# FBMiniLEDStrip.net
KiCad netlist of a schematic drawn in EAGLE
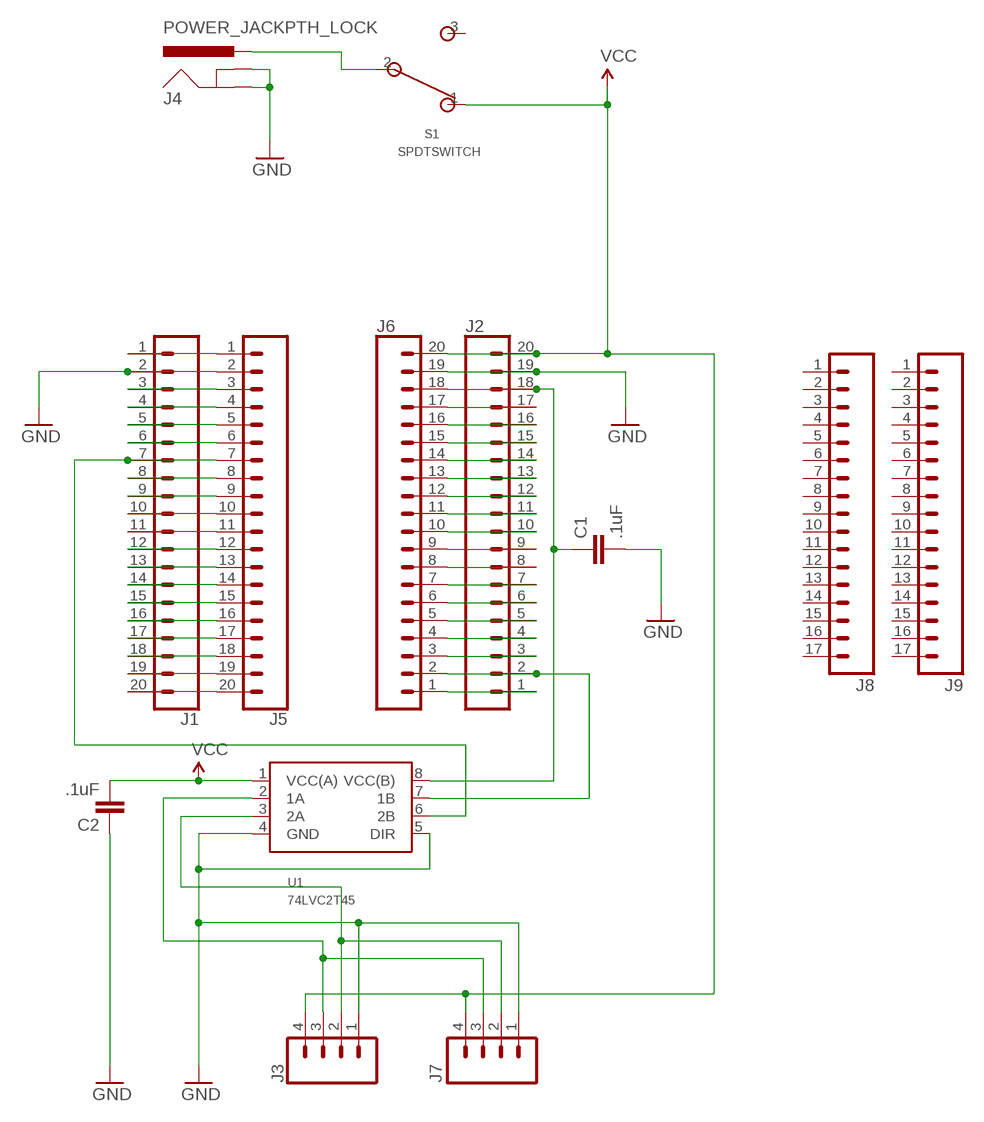
[diagram p0: schematic, sheet 1]

(export (version "E")
  (design (tool "Eeschema 10.0.6"))
  (components
    (comp (ref "C1")
      (value ".1uF")
      (footprint "eagle-import:0603-CAP")
      (libsource (lib "eagle-import") (part "CAP0603-CAP"))
    )
    (comp (ref "C2")
      (value ".1uF")
      (footprint "eagle-import:0603-CAP")
      (libsource (lib "eagle-import") (part "CAP0603-CAP"))
    )
    (comp (ref "J1")
      (value "CONN_20")
      (footprint "eagle-import:1X20")
      (libsource (lib "eagle-import") (part "CONN_20"))
    )
    (comp (ref "J2")
      (value "CONN_20")
      (footprint "eagle-import:1X20")
      (libsource (lib "eagle-import") (part "CONN_20"))
    )
    (comp (ref "J3")
      (value "CONN_04SCREW")
      (footprint "eagle-import:SCREWTERMINAL-3.5MM-4@1")
      (libsource (lib "eagle-import") (part "CONN_04SCREW"))
    )
    (comp (ref "J4")
      (value "POWER_JACKPTH_LOCK")
      (footprint "eagle-import:POWER_JACK_PTH_LOCK")
      (libsource (lib "eagle-import") (part "POWER_JACKPTH_LOCK"))
    )
    (comp (ref "J5")
      (value "CONN_20")
      (footprint "eagle-import:1X20")
      (libsource (lib "eagle-import") (part "CONN_20"))
    )
    (comp (ref "J6")
      (value "CONN_20")
      (footprint "eagle-import:1X20")
      (libsource (lib "eagle-import") (part "CONN_20"))
    )
    (comp (ref "J7")
      (value "M04PTH")
      (footprint "eagle-import:1X04")
      (libsource (lib "eagle-import") (part "M04PTH"))
    )
    (comp (ref "J8")
      (value "M17")
      (footprint "eagle-import:1X17")
      (libsource (lib "eagle-import") (part "M17"))
    )
    (comp (ref "J9")
      (value "M17")
      (footprint "eagle-import:1X17")
      (libsource (lib "eagle-import") (part "M17"))
    )
    (comp (ref "S1")
      (value "SPDTSWITCH")
      (footprint "eagle-import:100SP1T1B4M2QE")
      (libsource (lib "eagle-import") (part "SPDTSWITCH"))
    )
    (comp (ref "U1")
      (value "74LVC2T45")
      (footprint "eagle-import:VSSOP8")
      (libsource (lib "eagle-import") (part "74LVC2T45"))
    )
  )
  (nets
    (net (code "1") (name "GND") (class "Default")
      (node (ref "C1") (pin "2") (pinfunction "2_2") (pintype "passive"))
      (node (ref "C2") (pin "1") (pinfunction "1_1") (pintype "passive"))
      (node (ref "J1") (pin "2") (pinfunction "2_2") (pintype "passive"))
      (node (ref "J2") (pin "19") (pinfunction "19_19") (pintype "passive"))
      (node (ref "J3") (pin "1") (pinfunction "1_1") (pintype "passive"))
      (node (ref "J4") (pin "GND") (pinfunction "GND_GND") (pintype "bidirectional"))
      (node (ref "J4") (pin "GNDBREAK") (pinfunction "GNDBREAK_GNDBREAK") (pintype "bidirectional"))
      (node (ref "J5") (pin "2") (pinfunction "2_2") (pintype "passive"))
      (node (ref "J6") (pin "19") (pinfunction "19_19") (pintype "passive"))
      (node (ref "J7") (pin "1") (pinfunction "1_1") (pintype "passive"))
      (node (ref "U1") (pin "4") (pinfunction "GND_4") (pintype "bidirectional"))
      (node (ref "U1") (pin "5") (pinfunction "DIR_5") (pintype "bidirectional"))
    )
    (net (code "2") (name "Net-(J1-Pad1)") (class "Default")
      (node (ref "J1") (pin "1") (pinfunction "1_1") (pintype "passive"))
      (node (ref "J5") (pin "1") (pinfunction "1_1") (pintype "passive"))
    )
    (net (code "3") (name "Net-(J1-Pad3)") (class "Default")
      (node (ref "J1") (pin "3") (pinfunction "3_3") (pintype "passive"))
      (node (ref "J5") (pin "3") (pinfunction "3_3") (pintype "passive"))
    )
    (net (code "4") (name "Net-(J1-Pad4)") (class "Default")
      (node (ref "J1") (pin "4") (pinfunction "4_4") (pintype "passive"))
      (node (ref "J5") (pin "4") (pinfunction "4_4") (pintype "passive"))
    )
    (net (code "5") (name "Net-(J1-Pad5)") (class "Default")
      (node (ref "J1") (pin "5") (pinfunction "5_5") (pintype "passive"))
      (node (ref "J5") (pin "5") (pinfunction "5_5") (pintype "passive"))
    )
    (net (code "6") (name "Net-(J1-Pad6)") (class "Default")
      (node (ref "J1") (pin "6") (pinfunction "6_6") (pintype "passive"))
      (node (ref "J5") (pin "6") (pinfunction "6_6") (pintype "passive"))
    )
    (net (code "7") (name "Net-(J1-Pad8)") (class "Default")
      (node (ref "J1") (pin "8") (pinfunction "8_8") (pintype "passive"))
      (node (ref "J5") (pin "8") (pinfunction "8_8") (pintype "passive"))
    )
    (net (code "8") (name "Net-(J1-Pad9)") (class "Default")
      (node (ref "J1") (pin "9") (pinfunction "9_9") (pintype "passive"))
      (node (ref "J5") (pin "9") (pinfunction "9_9") (pintype "passive"))
    )
    (net (code "9") (name "Net-(J1-Pad10)") (class "Default")
      (node (ref "J1") (pin "10") (pinfunction "10_10") (pintype "passive"))
      (node (ref "J5") (pin "10") (pinfunction "10_10") (pintype "passive"))
    )
    (net (code "10") (name "Net-(J1-Pad11)") (class "Default")
      (node (ref "J1") (pin "11") (pinfunction "11_11") (pintype "passive"))
      (node (ref "J5") (pin "11") (pinfunction "11_11") (pintype "passive"))
    )
    (net (code "11") (name "Net-(J1-Pad12)") (class "Default")
      (node (ref "J1") (pin "12") (pinfunction "12_12") (pintype "passive"))
      (node (ref "J5") (pin "12") (pinfunction "12_12") (pintype "passive"))
    )
    (net (code "12") (name "Net-(J1-Pad13)") (class "Default")
      (node (ref "J1") (pin "13") (pinfunction "13_13") (pintype "passive"))
      (node (ref "J5") (pin "13") (pinfunction "13_13") (pintype "passive"))
    )
    (net (code "13") (name "Net-(J1-Pad14)") (class "Default")
      (node (ref "J1") (pin "14") (pinfunction "14_14") (pintype "passive"))
      (node (ref "J5") (pin "14") (pinfunction "14_14") (pintype "passive"))
    )
    (net (code "14") (name "Net-(J1-Pad15)") (class "Default")
      (node (ref "J1") (pin "15") (pinfunction "15_15") (pintype "passive"))
      (node (ref "J5") (pin "15") (pinfunction "15_15") (pintype "passive"))
    )
    (net (code "15") (name "Net-(J1-Pad16)") (class "Default")
      (node (ref "J1") (pin "16") (pinfunction "16_16") (pintype "passive"))
      (node (ref "J5") (pin "16") (pinfunction "16_16") (pintype "passive"))
    )
    (net (code "16") (name "Net-(J1-Pad17)") (class "Default")
      (node (ref "J1") (pin "17") (pinfunction "17_17") (pintype "passive"))
      (node (ref "J5") (pin "17") (pinfunction "17_17") (pintype "passive"))
    )
    (net (code "17") (name "Net-(J1-Pad18)") (class "Default")
      (node (ref "J1") (pin "18") (pinfunction "18_18") (pintype "passive"))
      (node (ref "J5") (pin "18") (pinfunction "18_18") (pintype "passive"))
    )
    (net (code "18") (name "Net-(J1-Pad19)") (class "Default")
      (node (ref "J1") (pin "19") (pinfunction "19_19") (pintype "passive"))
      (node (ref "J5") (pin "19") (pinfunction "19_19") (pintype "passive"))
    )
    (net (code "19") (name "Net-(J1-Pad20)") (class "Default")
      (node (ref "J1") (pin "20") (pinfunction "20_20") (pintype "passive"))
      (node (ref "J5") (pin "20") (pinfunction "20_20") (pintype "passive"))
    )
    (net (code "20") (name "Net-(J2-Pad1)") (class "Default")
      (node (ref "J2") (pin "1") (pinfunction "1_1") (pintype "passive"))
      (node (ref "J6") (pin "1") (pinfunction "1_1") (pintype "passive"))
    )
    (net (code "21") (name "Net-(J2-Pad3)") (class "Default")
      (node (ref "J2") (pin "3") (pinfunction "3_3") (pintype "passive"))
      (node (ref "J6") (pin "3") (pinfunction "3_3") (pintype "passive"))
    )
    (net (code "22") (name "Net-(J2-Pad4)") (class "Default")
      (node (ref "J2") (pin "4") (pinfunction "4_4") (pintype "passive"))
      (node (ref "J6") (pin "4") (pinfunction "4_4") (pintype "passive"))
    )
    (net (code "23") (name "Net-(J2-Pad5)") (class "Default")
      (node (ref "J2") (pin "5") (pinfunction "5_5") (pintype "passive"))
      (node (ref "J6") (pin "5") (pinfunction "5_5") (pintype "passive"))
    )
    (net (code "24") (name "Net-(J2-Pad6)") (class "Default")
      (node (ref "J2") (pin "6") (pinfunction "6_6") (pintype "passive"))
      (node (ref "J6") (pin "6") (pinfunction "6_6") (pintype "passive"))
    )
    (net (code "25") (name "Net-(J2-Pad7)") (class "Default")
      (node (ref "J2") (pin "7") (pinfunction "7_7") (pintype "passive"))
      (node (ref "J6") (pin "7") (pinfunction "7_7") (pintype "passive"))
    )
    (net (code "26") (name "Net-(J2-Pad8)") (class "Default")
      (node (ref "J2") (pin "8") (pinfunction "8_8") (pintype "passive"))
      (node (ref "J6") (pin "8") (pinfunction "8_8") (pintype "passive"))
    )
    (net (code "27") (name "Net-(J2-Pad9)") (class "Default")
      (node (ref "J2") (pin "9") (pinfunction "9_9") (pintype "passive"))
      (node (ref "J6") (pin "9") (pinfunction "9_9") (pintype "passive"))
    )
    (net (code "28") (name "Net-(J2-Pad10)") (class "Default")
      (node (ref "J2") (pin "10") (pinfunction "10_10") (pintype "passive"))
      (node (ref "J6") (pin "10") (pinfunction "10_10") (pintype "passive"))
    )
    (net (code "29") (name "Net-(J2-Pad11)") (class "Default")
      (node (ref "J2") (pin "11") (pinfunction "11_11") (pintype "passive"))
      (node (ref "J6") (pin "11") (pinfunction "11_11") (pintype "passive"))
    )
    (net (code "30") (name "Net-(J2-Pad12)") (class "Default")
      (node (ref "J2") (pin "12") (pinfunction "12_12") (pintype "passive"))
      (node (ref "J6") (pin "12") (pinfunction "12_12") (pintype "passive"))
    )
    (net (code "31") (name "Net-(J2-Pad13)") (class "Default")
      (node (ref "J2") (pin "13") (pinfunction "13_13") (pintype "passive"))
      (node (ref "J6") (pin "13") (pinfunction "13_13") (pintype "passive"))
    )
    (net (code "32") (name "Net-(J2-Pad14)") (class "Default")
      (node (ref "J2") (pin "14") (pinfunction "14_14") (pintype "passive"))
      (node (ref "J6") (pin "14") (pinfunction "14_14") (pintype "passive"))
    )
    (net (code "33") (name "Net-(J2-Pad15)") (class "Default")
      (node (ref "J2") (pin "15") (pinfunction "15_15") (pintype "passive"))
      (node (ref "J6") (pin "15") (pinfunction "15_15") (pintype "passive"))
    )
    (net (code "34") (name "Net-(J2-Pad16)") (class "Default")
      (node (ref "J2") (pin "16") (pinfunction "16_16") (pintype "passive"))
      (node (ref "J6") (pin "16") (pinfunction "16_16") (pintype "passive"))
    )
    (net (code "35") (name "Net-(J2-Pad17)") (class "Default")
      (node (ref "J2") (pin "17") (pinfunction "17_17") (pintype "passive"))
      (node (ref "J6") (pin "17") (pinfunction "17_17") (pintype "passive"))
    )
    (net (code "36") (name "Net-(S1-P$2)") (class "Default")
      (node (ref "J4") (pin "PWR") (pinfunction "PWR_PWR") (pintype "bidirectional"))
      (node (ref "S1") (pin "2") (pinfunction "P$2_2") (pintype "bidirectional"))
    )
    (net (code "37") (name "Net-(U1-1A)") (class "Default")
      (node (ref "J3") (pin "3") (pinfunction "3_3") (pintype "passive"))
      (node (ref "J7") (pin "3") (pinfunction "3_3") (pintype "passive"))
      (node (ref "U1") (pin "2") (pinfunction "1A_2") (pintype "bidirectional"))
    )
    (net (code "38") (name "Net-(U1-1B)") (class "Default")
      (node (ref "J2") (pin "2") (pinfunction "2_2") (pintype "passive"))
      (node (ref "J6") (pin "2") (pinfunction "2_2") (pintype "passive"))
      (node (ref "U1") (pin "7") (pinfunction "1B_7") (pintype "bidirectional"))
    )
    (net (code "39") (name "Net-(U1-2A)") (class "Default")
      (node (ref "J3") (pin "2") (pinfunction "2_2") (pintype "passive"))
      (node (ref "J7") (pin "2") (pinfunction "2_2") (pintype "passive"))
      (node (ref "U1") (pin "3") (pinfunction "2A_3") (pintype "bidirectional"))
    )
    (net (code "40") (name "Net-(U1-2B)") (class "Default")
      (node (ref "J1") (pin "7") (pinfunction "7_7") (pintype "passive"))
      (node (ref "J5") (pin "7") (pinfunction "7_7") (pintype "passive"))
      (node (ref "U1") (pin "6") (pinfunction "2B_6") (pintype "bidirectional"))
    )
    (net (code "41") (name "Net-(U1-VCC(B))") (class "Default")
      (node (ref "C1") (pin "1") (pinfunction "1_1") (pintype "passive"))
      (node (ref "J2") (pin "18") (pinfunction "18_18") (pintype "passive"))
      (node (ref "J6") (pin "18") (pinfunction "18_18") (pintype "passive"))
      (node (ref "U1") (pin "8") (pinfunction "VCC(B)_8") (pintype "bidirectional"))
    )
    (net (code "42") (name "VCC") (class "Default")
      (node (ref "C2") (pin "2") (pinfunction "2_2") (pintype "passive"))
      (node (ref "J2") (pin "20") (pinfunction "20_20") (pintype "passive"))
      (node (ref "J3") (pin "4") (pinfunction "4_4") (pintype "passive"))
      (node (ref "J6") (pin "20") (pinfunction "20_20") (pintype "passive"))
      (node (ref "J7") (pin "4") (pinfunction "4_4") (pintype "passive"))
      (node (ref "S1") (pin "1") (pinfunction "P$1_1") (pintype "bidirectional"))
      (node (ref "U1") (pin "1") (pinfunction "VCC(A)_1") (pintype "bidirectional"))
    )
    (net (code "43") (name "unconnected-(J8-Pad1)") (class "Default")
      (node (ref "J8") (pin "1") (pinfunction "1_1") (pintype "passive"))
    )
    (net (code "44") (name "unconnected-(J8-Pad2)") (class "Default")
      (node (ref "J8") (pin "2") (pinfunction "2_2") (pintype "passive"))
    )
    (net (code "45") (name "unconnected-(J8-Pad3)") (class "Default")
      (node (ref "J8") (pin "3") (pinfunction "3_3") (pintype "passive"))
    )
    (net (code "46") (name "unconnected-(J8-Pad4)") (class "Default")
      (node (ref "J8") (pin "4") (pinfunction "4_4") (pintype "passive"))
    )
    (net (code "47") (name "unconnected-(J8-Pad5)") (class "Default")
      (node (ref "J8") (pin "5") (pinfunction "5_5") (pintype "passive"))
    )
    (net (code "48") (name "unconnected-(J8-Pad6)") (class "Default")
      (node (ref "J8") (pin "6") (pinfunction "6_6") (pintype "passive"))
    )
    (net (code "49") (name "unconnected-(J8-Pad7)") (class "Default")
      (node (ref "J8") (pin "7") (pinfunction "7_7") (pintype "passive"))
    )
    (net (code "50") (name "unconnected-(J8-Pad8)") (class "Default")
      (node (ref "J8") (pin "8") (pinfunction "8_8") (pintype "passive"))
    )
    (net (code "51") (name "unconnected-(J8-Pad9)") (class "Default")
      (node (ref "J8") (pin "9") (pinfunction "9_9") (pintype "passive"))
    )
    (net (code "52") (name "unconnected-(J8-Pad10)") (class "Default")
      (node (ref "J8") (pin "10") (pinfunction "10_10") (pintype "passive"))
    )
    (net (code "53") (name "unconnected-(J8-Pad11)") (class "Default")
      (node (ref "J8") (pin "11") (pinfunction "11_11") (pintype "passive"))
    )
    (net (code "54") (name "unconnected-(J8-Pad12)") (class "Default")
      (node (ref "J8") (pin "12") (pinfunction "12_12") (pintype "passive"))
    )
    (net (code "55") (name "unconnected-(J8-Pad13)") (class "Default")
      (node (ref "J8") (pin "13") (pinfunction "13_13") (pintype "passive"))
    )
    (net (code "56") (name "unconnected-(J8-Pad14)") (class "Default")
      (node (ref "J8") (pin "14") (pinfunction "14_14") (pintype "passive"))
    )
    (net (code "57") (name "unconnected-(J8-Pad15)") (class "Default")
      (node (ref "J8") (pin "15") (pinfunction "15_15") (pintype "passive"))
    )
    (net (code "58") (name "unconnected-(J8-Pad16)") (class "Default")
      (node (ref "J8") (pin "16") (pinfunction "16_16") (pintype "passive"))
    )
    (net (code "59") (name "unconnected-(J8-Pad17)") (class "Default")
      (node (ref "J8") (pin "17") (pinfunction "17_17") (pintype "passive"))
    )
    (net (code "60") (name "unconnected-(J9-Pad1)") (class "Default")
      (node (ref "J9") (pin "1") (pinfunction "1_1") (pintype "passive"))
    )
    (net (code "61") (name "unconnected-(J9-Pad2)") (class "Default")
      (node (ref "J9") (pin "2") (pinfunction "2_2") (pintype "passive"))
    )
    (net (code "62") (name "unconnected-(J9-Pad3)") (class "Default")
      (node (ref "J9") (pin "3") (pinfunction "3_3") (pintype "passive"))
    )
    (net (code "63") (name "unconnected-(J9-Pad4)") (class "Default")
      (node (ref "J9") (pin "4") (pinfunction "4_4") (pintype "passive"))
    )
    (net (code "64") (name "unconnected-(J9-Pad5)") (class "Default")
      (node (ref "J9") (pin "5") (pinfunction "5_5") (pintype "passive"))
    )
    (net (code "65") (name "unconnected-(J9-Pad6)") (class "Default")
      (node (ref "J9") (pin "6") (pinfunction "6_6") (pintype "passive"))
    )
    (net (code "66") (name "unconnected-(J9-Pad7)") (class "Default")
      (node (ref "J9") (pin "7") (pinfunction "7_7") (pintype "passive"))
    )
    (net (code "67") (name "unconnected-(J9-Pad8)") (class "Default")
      (node (ref "J9") (pin "8") (pinfunction "8_8") (pintype "passive"))
    )
    (net (code "68") (name "unconnected-(J9-Pad9)") (class "Default")
      (node (ref "J9") (pin "9") (pinfunction "9_9") (pintype "passive"))
    )
    (net (code "69") (name "unconnected-(J9-Pad10)") (class "Default")
      (node (ref "J9") (pin "10") (pinfunction "10_10") (pintype "passive"))
    )
    (net (code "70") (name "unconnected-(J9-Pad11)") (class "Default")
      (node (ref "J9") (pin "11") (pinfunction "11_11") (pintype "passive"))
    )
    (net (code "71") (name "unconnected-(J9-Pad12)") (class "Default")
      (node (ref "J9") (pin "12") (pinfunction "12_12") (pintype "passive"))
    )
    (net (code "72") (name "unconnected-(J9-Pad13)") (class "Default")
      (node (ref "J9") (pin "13") (pinfunction "13_13") (pintype "passive"))
    )
    (net (code "73") (name "unconnected-(J9-Pad14)") (class "Default")
      (node (ref "J9") (pin "14") (pinfunction "14_14") (pintype "passive"))
    )
    (net (code "74") (name "unconnected-(J9-Pad15)") (class "Default")
      (node (ref "J9") (pin "15") (pinfunction "15_15") (pintype "passive"))
    )
    (net (code "75") (name "unconnected-(J9-Pad16)") (class "Default")
      (node (ref "J9") (pin "16") (pinfunction "16_16") (pintype "passive"))
    )
    (net (code "76") (name "unconnected-(J9-Pad17)") (class "Default")
      (node (ref "J9") (pin "17") (pinfunction "17_17") (pintype "passive"))
    )
    (net (code "77") (name "unconnected-(S1-P$3-Pad3)") (class "Default")
      (node (ref "S1") (pin "3") (pinfunction "P$3_3") (pintype "bidirectional"))
    )
  )
)
